# N64_RX_V2_0.net
KiCad netlist of a schematic drawn in EAGLE
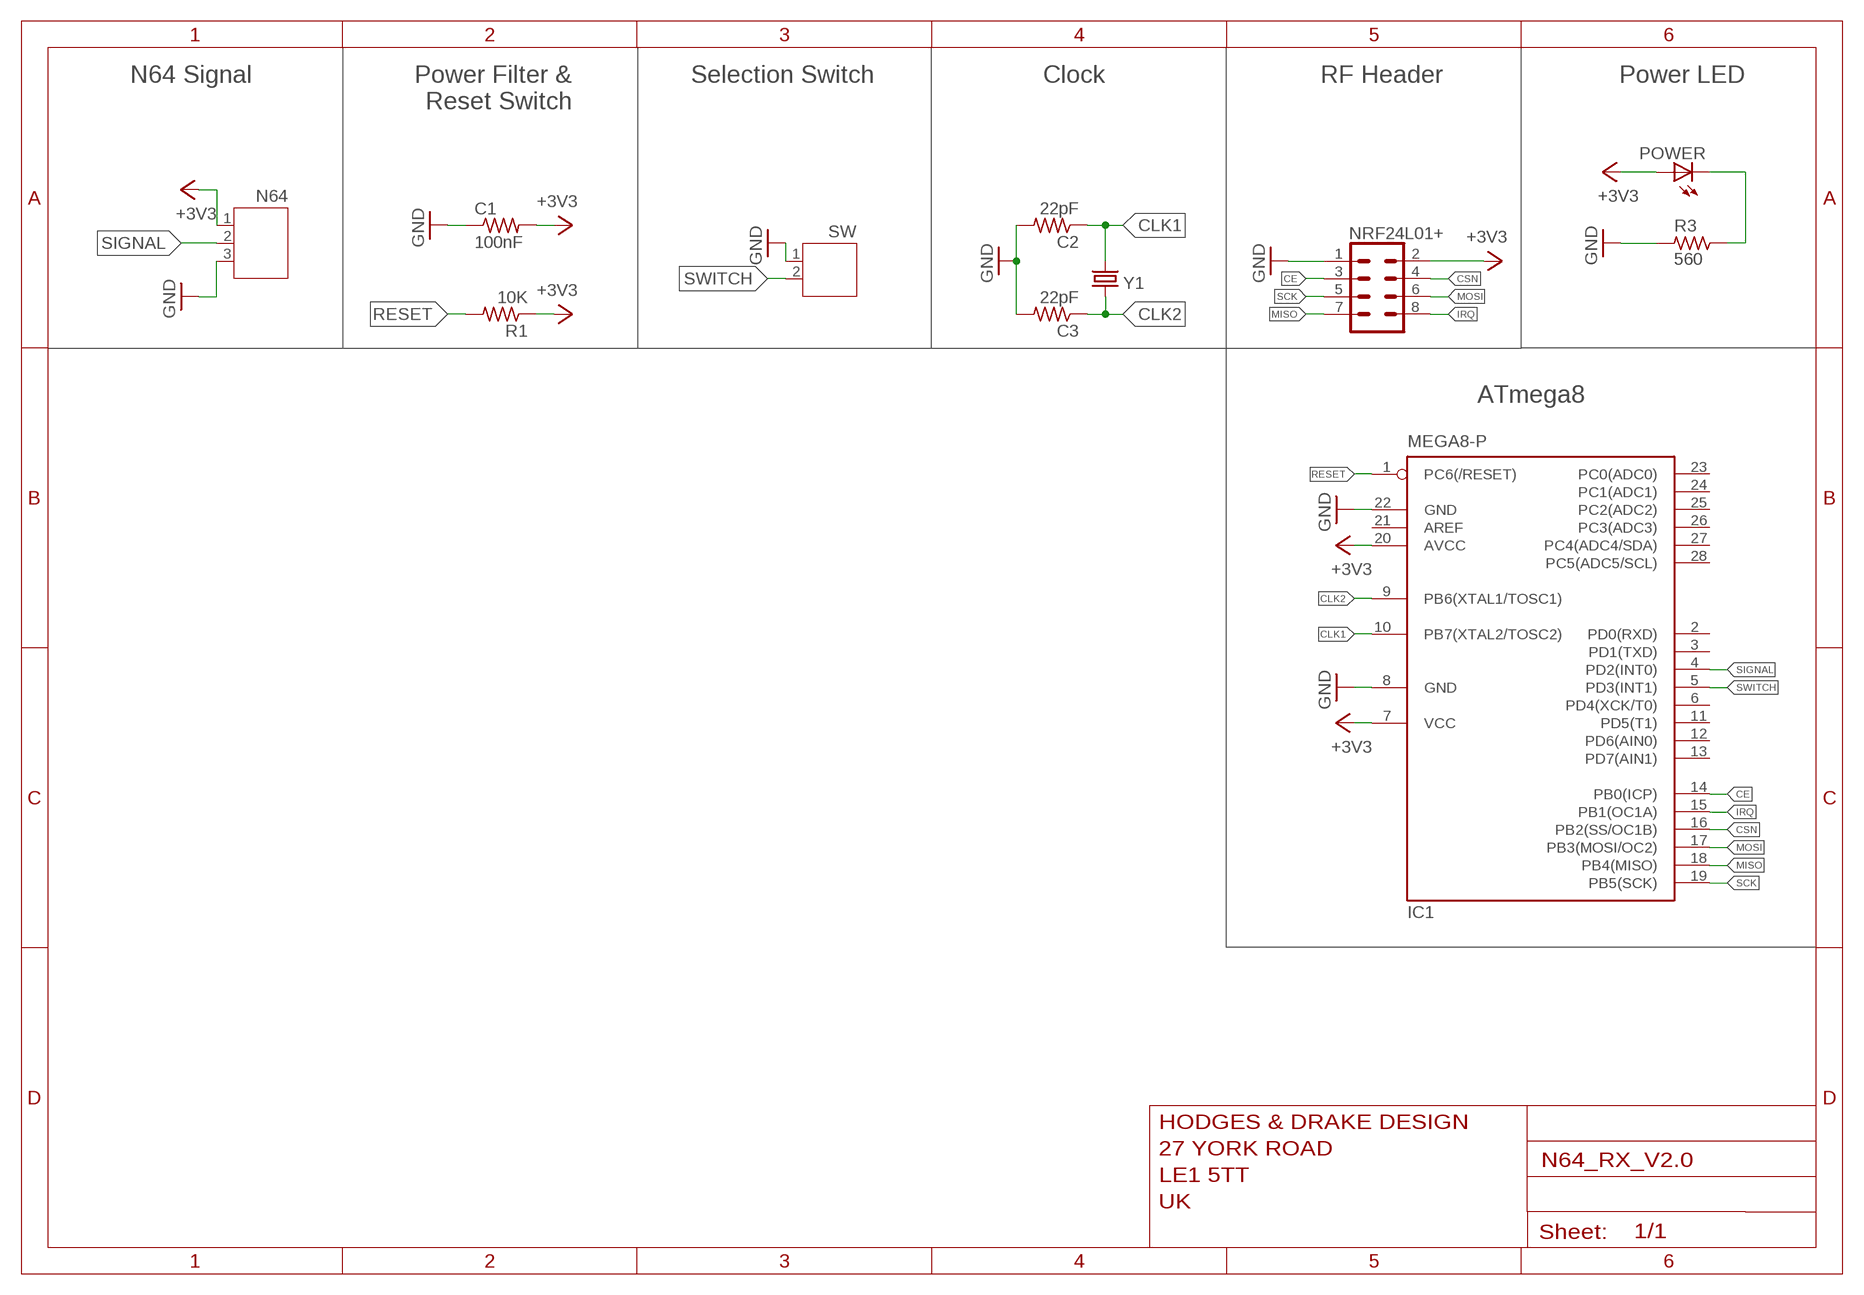
[diagram p0: schematic, sheet 1]

(export (version "E")
  (design (tool "Eeschema 10.0.6"))
  (components
    (comp (ref "C1")
      (value "100nF")
      (footprint "eagle-import:0805-THM")
      (libsource (lib "eagle-import") (part "FLIPFLOP-RES"))
    )
    (comp (ref "C2")
      (value "22pF")
      (footprint "eagle-import:0805-THM")
      (libsource (lib "eagle-import") (part "FLIPFLOP-RES"))
    )
    (comp (ref "C3")
      (value "22pF")
      (footprint "eagle-import:0805-THM")
      (libsource (lib "eagle-import") (part "FLIPFLOP-RES"))
    )
    (comp (ref "IC1")
      (value "MEGA8-P")
      (footprint "eagle-import:DIL28-3")
      (libsource (lib "eagle-import") (part "MEGA8-P"))
    )
    (comp (ref "N64")
      (value "JST-PH3TH")
      (footprint "eagle-import:JST-PH3")
      (libsource (lib "eagle-import") (part "JST-PH3TH"))
    )
    (comp (ref "NRF24L01+")
      (value "CONN_04X2")
      (footprint "eagle-import:2X4")
      (libsource (lib "eagle-import") (part "CONN_04X2"))
    )
    (comp (ref "POWER")
      (value "LEDCHIPLED_0805")
      (footprint "eagle-import:CHIPLED_0805")
      (libsource (lib "eagle-import") (part "LEDCHIPLED_0805"))
    )
    (comp (ref "R1")
      (value "10K")
      (footprint "eagle-import:0805-THM")
      (libsource (lib "eagle-import") (part "FLIPFLOP-RES"))
    )
    (comp (ref "R3")
      (value "560")
      (footprint "eagle-import:R0805")
      (libsource (lib "eagle-import") (part "R_0805"))
    )
    (comp (ref "SW")
      (value "JST-PH2TH")
      (footprint "eagle-import:JST-PH2")
      (libsource (lib "eagle-import") (part "JST-PH2TH"))
    )
    (comp (ref "Y1")
      (value "CRYSTALHC49S")
      (footprint "eagle-import:HC49_S")
      (libsource (lib "eagle-import") (part "CRYSTALHC49S"))
    )
  )
  (nets
    (net (code "1") (name "+3V3") (class "Default")
      (node (ref "C1") (pin "2") (pinfunction "2_2") (pintype "passive"))
      (node (ref "IC1") (pin "20") (pinfunction "AVCC_20") (pintype "power_in"))
      (node (ref "IC1") (pin "7") (pinfunction "VCC_7") (pintype "power_in"))
      (node (ref "N64") (pin "1") (pinfunction "1_1") (pintype "passive"))
      (node (ref "NRF24L01+") (pin "2") (pinfunction "2_2") (pintype "passive"))
      (node (ref "POWER") (pin "A") (pinfunction "A_A") (pintype "passive"))
      (node (ref "R1") (pin "1") (pinfunction "1_1") (pintype "passive"))
    )
    (net (code "2") (name "CE") (class "Default")
      (node (ref "IC1") (pin "14") (pinfunction "PB0(ICP)_14") (pintype "bidirectional"))
      (node (ref "NRF24L01+") (pin "3") (pinfunction "3_3") (pintype "passive"))
    )
    (net (code "3") (name "CLK1") (class "Default")
      (node (ref "C2") (pin "1") (pinfunction "1_1") (pintype "passive"))
      (node (ref "IC1") (pin "10") (pinfunction "PB7(XTAL2/TOSC2)_10") (pintype "bidirectional"))
      (node (ref "Y1") (pin "2") (pinfunction "2_2") (pintype "passive"))
    )
    (net (code "4") (name "CLK2") (class "Default")
      (node (ref "C3") (pin "1") (pinfunction "1_1") (pintype "passive"))
      (node (ref "IC1") (pin "9") (pinfunction "PB6(XTAL1/TOSC1)_9") (pintype "bidirectional"))
      (node (ref "Y1") (pin "1") (pinfunction "1_1") (pintype "passive"))
    )
    (net (code "5") (name "CSN") (class "Default")
      (node (ref "IC1") (pin "16") (pinfunction "PB2(SS/OC1B)_16") (pintype "bidirectional"))
      (node (ref "NRF24L01+") (pin "4") (pinfunction "4_4") (pintype "passive"))
    )
    (net (code "6") (name "GND") (class "Default")
      (node (ref "C1") (pin "1") (pinfunction "1_1") (pintype "passive"))
      (node (ref "C2") (pin "2") (pinfunction "2_2") (pintype "passive"))
      (node (ref "C3") (pin "2") (pinfunction "2_2") (pintype "passive"))
      (node (ref "IC1") (pin "22") (pinfunction "GND_22") (pintype "power_in"))
      (node (ref "IC1") (pin "8") (pinfunction "GND_8") (pintype "power_in"))
      (node (ref "N64") (pin "3") (pinfunction "3_3") (pintype "passive"))
      (node (ref "NRF24L01+") (pin "1") (pinfunction "1_1") (pintype "passive"))
      (node (ref "R3") (pin "1") (pinfunction "1_1") (pintype "passive"))
      (node (ref "SW") (pin "1") (pinfunction "1_1") (pintype "passive"))
    )
    (net (code "7") (name "IRQ") (class "Default")
      (node (ref "IC1") (pin "15") (pinfunction "PB1(OC1A)_15") (pintype "bidirectional"))
      (node (ref "NRF24L01+") (pin "8") (pinfunction "8_8") (pintype "passive"))
    )
    (net (code "8") (name "MISO") (class "Default")
      (node (ref "IC1") (pin "18") (pinfunction "PB4(MISO)_18") (pintype "bidirectional"))
      (node (ref "NRF24L01+") (pin "7") (pinfunction "7_7") (pintype "passive"))
    )
    (net (code "9") (name "MOSI") (class "Default")
      (node (ref "IC1") (pin "17") (pinfunction "PB3(MOSI/OC2)_17") (pintype "bidirectional"))
      (node (ref "NRF24L01+") (pin "6") (pinfunction "6_6") (pintype "passive"))
    )
    (net (code "10") (name "Net-(POWER-PadC)") (class "Default")
      (node (ref "POWER") (pin "C") (pinfunction "C_C") (pintype "passive"))
      (node (ref "R3") (pin "2") (pinfunction "2_2") (pintype "passive"))
    )
    (net (code "11") (name "RESET") (class "Default")
      (node (ref "IC1") (pin "1") (pinfunction "PC6(/RESET)_1") (pintype "bidirectional"))
      (node (ref "R1") (pin "2") (pinfunction "2_2") (pintype "passive"))
    )
    (net (code "12") (name "SCK") (class "Default")
      (node (ref "IC1") (pin "19") (pinfunction "PB5(SCK)_19") (pintype "bidirectional"))
      (node (ref "NRF24L01+") (pin "5") (pinfunction "5_5") (pintype "passive"))
    )
    (net (code "13") (name "SIGNAL") (class "Default")
      (node (ref "IC1") (pin "4") (pinfunction "PD2(INT0)_4") (pintype "bidirectional"))
      (node (ref "N64") (pin "2") (pinfunction "2_2") (pintype "passive"))
    )
    (net (code "14") (name "SWITCH") (class "Default")
      (node (ref "IC1") (pin "5") (pinfunction "PD3(INT1)_5") (pintype "bidirectional"))
      (node (ref "SW") (pin "2") (pinfunction "2_2") (pintype "passive"))
    )
    (net (code "15") (name "unconnected-(IC1-AREF-Pad21)") (class "Default")
      (node (ref "IC1") (pin "21") (pinfunction "AREF_21") (pintype "passive"))
    )
    (net (code "16") (name "unconnected-(IC1-PC0(ADC0)-Pad23)") (class "Default")
      (node (ref "IC1") (pin "23") (pinfunction "PC0(ADC0)_23") (pintype "bidirectional"))
    )
    (net (code "17") (name "unconnected-(IC1-PC1(ADC1)-Pad24)") (class "Default")
      (node (ref "IC1") (pin "24") (pinfunction "PC1(ADC1)_24") (pintype "bidirectional"))
    )
    (net (code "18") (name "unconnected-(IC1-PC2(ADC2)-Pad25)") (class "Default")
      (node (ref "IC1") (pin "25") (pinfunction "PC2(ADC2)_25") (pintype "bidirectional"))
    )
    (net (code "19") (name "unconnected-(IC1-PC3(ADC3)-Pad26)") (class "Default")
      (node (ref "IC1") (pin "26") (pinfunction "PC3(ADC3)_26") (pintype "bidirectional"))
    )
    (net (code "20") (name "unconnected-(IC1-PC4(ADC4{slash}SDA)-Pad27)") (class "Default")
      (node (ref "IC1") (pin "27") (pinfunction "PC4(ADC4/SDA)_27") (pintype "bidirectional"))
    )
    (net (code "21") (name "unconnected-(IC1-PC5(ADC5{slash}SCL)-Pad28)") (class "Default")
      (node (ref "IC1") (pin "28") (pinfunction "PC5(ADC5/SCL)_28") (pintype "bidirectional"))
    )
    (net (code "22") (name "unconnected-(IC1-PD0(RXD)-Pad2)") (class "Default")
      (node (ref "IC1") (pin "2") (pinfunction "PD0(RXD)_2") (pintype "bidirectional"))
    )
    (net (code "23") (name "unconnected-(IC1-PD1(TXD)-Pad3)") (class "Default")
      (node (ref "IC1") (pin "3") (pinfunction "PD1(TXD)_3") (pintype "bidirectional"))
    )
    (net (code "24") (name "unconnected-(IC1-PD4(XCK{slash}T0)-Pad6)") (class "Default")
      (node (ref "IC1") (pin "6") (pinfunction "PD4(XCK/T0)_6") (pintype "bidirectional"))
    )
    (net (code "25") (name "unconnected-(IC1-PD5(T1)-Pad11)") (class "Default")
      (node (ref "IC1") (pin "11") (pinfunction "PD5(T1)_11") (pintype "bidirectional"))
    )
    (net (code "26") (name "unconnected-(IC1-PD6(AIN0)-Pad12)") (class "Default")
      (node (ref "IC1") (pin "12") (pinfunction "PD6(AIN0)_12") (pintype "bidirectional"))
    )
    (net (code "27") (name "unconnected-(IC1-PD7(AIN1)-Pad13)") (class "Default")
      (node (ref "IC1") (pin "13") (pinfunction "PD7(AIN1)_13") (pintype "bidirectional"))
    )
  )
)
